# SHT_Test_Module.net
KiCad netlist of a schematic drawn in EAGLE
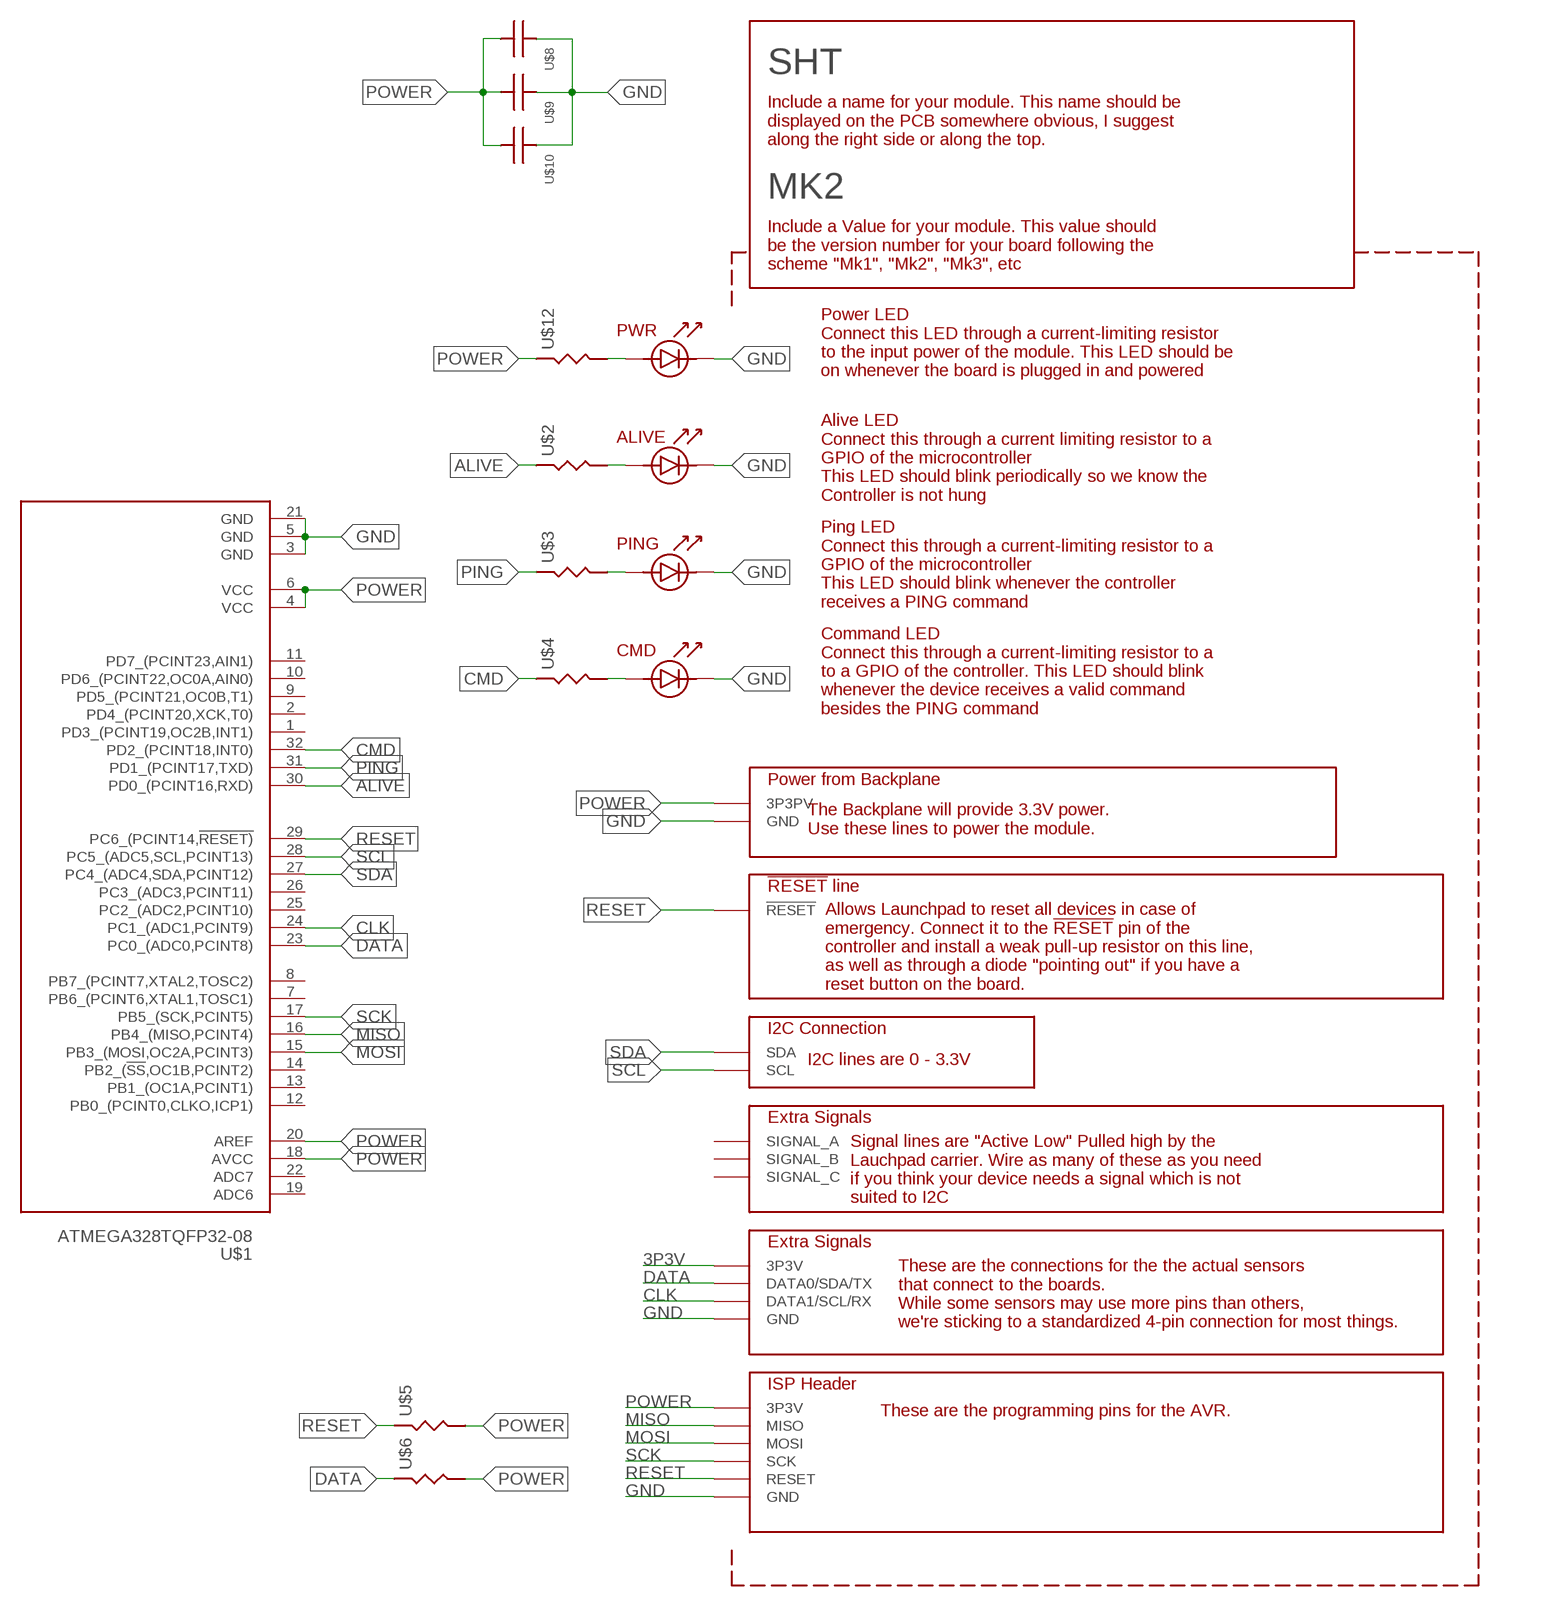
[diagram p0: schematic, sheet 1]

(export (version "E")
  (design (tool "Eeschema 10.0.6"))
  (components
    (comp (ref "SHT")
      (value "MK2")
      (footprint "eagle-import:SENSOR_MODULE_MK1")
      (libsource (lib "eagle-import") (part "SENSOR_MODULE_MK1"))
    )
    (comp (ref "U$1")
      (value "ATMEGA328TQFP32-08")
      (footprint "eagle-import:TQFP32-08")
      (libsource (lib "eagle-import") (part "ATMEGA328TQFP32-08"))
    )
    (comp (ref "U$2")
      (value "RESISTOR")
      (footprint "eagle-import:0805_STACKPOLERESISTOR")
      (libsource (lib "eagle-import") (part "RESISTOR"))
    )
    (comp (ref "U$3")
      (value "RESISTOR")
      (footprint "eagle-import:0805_STACKPOLERESISTOR")
      (libsource (lib "eagle-import") (part "RESISTOR"))
    )
    (comp (ref "U$4")
      (value "RESISTOR")
      (footprint "eagle-import:0805_STACKPOLERESISTOR")
      (libsource (lib "eagle-import") (part "RESISTOR"))
    )
    (comp (ref "U$5")
      (value "RESISTOR")
      (footprint "eagle-import:0805_STACKPOLERESISTOR")
      (libsource (lib "eagle-import") (part "RESISTOR"))
    )
    (comp (ref "U$6")
      (value "RESISTOR")
      (footprint "eagle-import:0805_STACKPOLERESISTOR")
      (libsource (lib "eagle-import") (part "RESISTOR"))
    )
    (comp (ref "U$8")
      (value "CAPACITOR-UNPOLARIZED0805")
      (footprint "eagle-import:0805_STACKPOLERESISTOR")
      (libsource (lib "eagle-import") (part "CAPACITOR-UNPOLARIZED0805"))
    )
    (comp (ref "U$9")
      (value "CAPACITOR-UNPOLARIZED0805")
      (footprint "eagle-import:0805_STACKPOLERESISTOR")
      (libsource (lib "eagle-import") (part "CAPACITOR-UNPOLARIZED0805"))
    )
    (comp (ref "U$10")
      (value "CAPACITOR-UNPOLARIZED0805")
      (footprint "eagle-import:0805_STACKPOLERESISTOR")
      (libsource (lib "eagle-import") (part "CAPACITOR-UNPOLARIZED0805"))
    )
    (comp (ref "U$12")
      (value "RESISTOR")
      (footprint "eagle-import:0805_STACKPOLERESISTOR")
      (libsource (lib "eagle-import") (part "RESISTOR"))
    )
  )
  (nets
    (net (code "1") (name "/3P3V") (class "Default")
      (node (ref "SHT") (pin "3P3V@2") (pinfunction "3P3V_3P3V@2") (pintype "bidirectional"))
      (node (ref "SHT") (pin "3P3V@3") (pinfunction "3P3V_3P3V@3") (pintype "bidirectional"))
    )
    (net (code "2") (name "ALIVE") (class "Default")
      (node (ref "U$1") (pin "30") (pinfunction "PD0_(PCINT16,RXD)_30") (pintype "bidirectional"))
      (node (ref "U$2") (pin "P$1") (pinfunction "P$1_P$1") (pintype "bidirectional"))
    )
    (net (code "3") (name "CLK") (class "Default")
      (node (ref "SHT") (pin "DATA1@1") (pinfunction "DATA1/SCL/RX_DATA1@1") (pintype "bidirectional"))
      (node (ref "SHT") (pin "DATA1@2") (pinfunction "DATA1/SCL/RX_DATA1@2") (pintype "bidirectional"))
      (node (ref "U$1") (pin "24") (pinfunction "PC1_(ADC1,PCINT9)_24") (pintype "bidirectional"))
    )
    (net (code "4") (name "CMD") (class "Default")
      (node (ref "U$1") (pin "32") (pinfunction "PD2_(PCINT18,INT0)_32") (pintype "bidirectional"))
      (node (ref "U$4") (pin "P$1") (pinfunction "P$1_P$1") (pintype "bidirectional"))
    )
    (net (code "5") (name "DATA") (class "Default")
      (node (ref "SHT") (pin "DATA0@1") (pinfunction "DATA0/SDA/TX_DATA0@1") (pintype "bidirectional"))
      (node (ref "SHT") (pin "DATA0@2") (pinfunction "DATA0/SDA/TX_DATA0@2") (pintype "bidirectional"))
      (node (ref "U$1") (pin "23") (pinfunction "PC0_(ADC0,PCINT8)_23") (pintype "bidirectional"))
      (node (ref "U$6") (pin "P$1") (pinfunction "P$1_P$1") (pintype "bidirectional"))
    )
    (net (code "6") (name "GND") (class "Default")
      (node (ref "SHT") (pin "ALIVELED_CATHODE") (pinfunction "ALIVELED_CATHODE_ALIVELED_CATHODE") (pintype "bidirectional"))
      (node (ref "SHT") (pin "CMDLED_CATHODE") (pinfunction "CMDLED_CATHODE_CMDLED_CATHODE") (pintype "bidirectional"))
      (node (ref "SHT") (pin "GND@1") (pinfunction "GND_GND@1") (pintype "bidirectional"))
      (node (ref "SHT") (pin "GND@2") (pinfunction "GND_GND@2") (pintype "bidirectional"))
      (node (ref "SHT") (pin "GND@3") (pinfunction "GND_GND@3") (pintype "bidirectional"))
      (node (ref "SHT") (pin "GND@4") (pinfunction "GND_GND@4") (pintype "bidirectional"))
      (node (ref "SHT") (pin "PINGLED_CATHODE") (pinfunction "PINGLED_CATHODE_PINGLED_CATHODE") (pintype "bidirectional"))
      (node (ref "SHT") (pin "PWRLED_CATHODE") (pinfunction "PWRLED_CATHODE_PWRLED_CATHODE") (pintype "bidirectional"))
      (node (ref "U$1") (pin "21") (pinfunction "GND_21") (pintype "bidirectional"))
      (node (ref "U$1") (pin "3") (pinfunction "GND_3") (pintype "bidirectional"))
      (node (ref "U$1") (pin "5") (pinfunction "GND_5") (pintype "bidirectional"))
      (node (ref "U$10") (pin "P$1") (pinfunction "P$1_P$1") (pintype "bidirectional"))
      (node (ref "U$8") (pin "P$1") (pinfunction "P$1_P$1") (pintype "bidirectional"))
      (node (ref "U$9") (pin "P$1") (pinfunction "P$1_P$1") (pintype "bidirectional"))
    )
    (net (code "7") (name "MISO") (class "Default")
      (node (ref "SHT") (pin "MISO") (pinfunction "MISO_MISO") (pintype "bidirectional"))
      (node (ref "U$1") (pin "16") (pinfunction "PB4_(MISO,PCINT4)_16") (pintype "bidirectional"))
    )
    (net (code "8") (name "MOSI") (class "Default")
      (node (ref "SHT") (pin "MOSI") (pinfunction "MOSI_MOSI") (pintype "bidirectional"))
      (node (ref "U$1") (pin "15") (pinfunction "PB3_(MOSI,OC2A,PCINT3)_15") (pintype "bidirectional"))
    )
    (net (code "9") (name "Net-(SHT-PadALIVELED_ANODE)") (class "Default")
      (node (ref "SHT") (pin "ALIVELED_ANODE") (pinfunction "ALIVELED_ANODE_ALIVELED_ANODE") (pintype "bidirectional"))
      (node (ref "U$2") (pin "P$2") (pinfunction "P$2_P$2") (pintype "bidirectional"))
    )
    (net (code "10") (name "Net-(SHT-PadCMDLED_ANODE)") (class "Default")
      (node (ref "SHT") (pin "CMDLED_ANODE") (pinfunction "CMDLED_ANODE_CMDLED_ANODE") (pintype "bidirectional"))
      (node (ref "U$4") (pin "P$2") (pinfunction "P$2_P$2") (pintype "bidirectional"))
    )
    (net (code "11") (name "Net-(SHT-PadPINGLED_ANODE)") (class "Default")
      (node (ref "SHT") (pin "PINGLED_ANODE") (pinfunction "PINGLED_ANODE_PINGLED_ANODE") (pintype "bidirectional"))
      (node (ref "U$3") (pin "P$2") (pinfunction "P$2_P$2") (pintype "bidirectional"))
    )
    (net (code "12") (name "Net-(SHT-PadPWRLED_ANODE)") (class "Default")
      (node (ref "SHT") (pin "PWRLED_ANODE") (pinfunction "PWRLED_ANODE_PWRLED_ANODE") (pintype "bidirectional"))
      (node (ref "U$12") (pin "P$2") (pinfunction "P$2_P$2") (pintype "bidirectional"))
    )
    (net (code "13") (name "PING") (class "Default")
      (node (ref "U$1") (pin "31") (pinfunction "PD1_(PCINT17,TXD)_31") (pintype "bidirectional"))
      (node (ref "U$3") (pin "P$1") (pinfunction "P$1_P$1") (pintype "bidirectional"))
    )
    (net (code "14") (name "POWER") (class "Default")
      (node (ref "SHT") (pin "3P3V@1") (pinfunction "3P3PV_3P3V@1") (pintype "bidirectional"))
      (node (ref "SHT") (pin "3P3V@4") (pinfunction "3P3V_3P3V@4") (pintype "bidirectional"))
      (node (ref "U$1") (pin "18") (pinfunction "AVCC_18") (pintype "bidirectional"))
      (node (ref "U$1") (pin "20") (pinfunction "AREF_20") (pintype "bidirectional"))
      (node (ref "U$1") (pin "4") (pinfunction "VCC_4") (pintype "bidirectional"))
      (node (ref "U$1") (pin "6") (pinfunction "VCC_6") (pintype "bidirectional"))
      (node (ref "U$10") (pin "P$2") (pinfunction "P$2_P$2") (pintype "bidirectional"))
      (node (ref "U$12") (pin "P$1") (pinfunction "P$1_P$1") (pintype "bidirectional"))
      (node (ref "U$5") (pin "P$2") (pinfunction "P$2_P$2") (pintype "bidirectional"))
      (node (ref "U$6") (pin "P$2") (pinfunction "P$2_P$2") (pintype "bidirectional"))
      (node (ref "U$8") (pin "P$2") (pinfunction "P$2_P$2") (pintype "bidirectional"))
      (node (ref "U$9") (pin "P$2") (pinfunction "P$2_P$2") (pintype "bidirectional"))
    )
    (net (code "15") (name "RESET") (class "Default")
      (node (ref "SHT") (pin "RESET@1") (pinfunction "~{RESET}_RESET@1") (pintype "bidirectional"))
      (node (ref "SHT") (pin "RESET@2") (pinfunction "RESET_RESET@2") (pintype "bidirectional"))
      (node (ref "U$1") (pin "29") (pinfunction "PC6_(PCINT14,~{RESET})_29") (pintype "bidirectional"))
      (node (ref "U$5") (pin "P$1") (pinfunction "P$1_P$1") (pintype "bidirectional"))
    )
    (net (code "16") (name "SCK") (class "Default")
      (node (ref "SHT") (pin "SCK") (pinfunction "SCK_SCK") (pintype "bidirectional"))
      (node (ref "U$1") (pin "17") (pinfunction "PB5_(SCK,PCINT5)_17") (pintype "bidirectional"))
    )
    (net (code "17") (name "SCL") (class "Default")
      (node (ref "SHT") (pin "SCL") (pinfunction "SCL_SCL") (pintype "bidirectional"))
      (node (ref "U$1") (pin "28") (pinfunction "PC5_(ADC5,SCL,PCINT13)_28") (pintype "bidirectional"))
    )
    (net (code "18") (name "SDA") (class "Default")
      (node (ref "SHT") (pin "SDA") (pinfunction "SDA_SDA") (pintype "bidirectional"))
      (node (ref "U$1") (pin "27") (pinfunction "PC4_(ADC4,SDA,PCINT12)_27") (pintype "bidirectional"))
    )
    (net (code "19") (name "unconnected-(SHT-SIGNAL_A-PadA)") (class "Default")
      (node (ref "SHT") (pin "A") (pinfunction "SIGNAL_A_A") (pintype "bidirectional"))
    )
    (net (code "20") (name "unconnected-(SHT-SIGNAL_B-PadB)") (class "Default")
      (node (ref "SHT") (pin "B") (pinfunction "SIGNAL_B_B") (pintype "bidirectional"))
    )
    (net (code "21") (name "unconnected-(SHT-SIGNAL_C-PadC)") (class "Default")
      (node (ref "SHT") (pin "C") (pinfunction "SIGNAL_C_C") (pintype "bidirectional"))
    )
    (net (code "22") (name "unconnected-(U$1-ADC6-Pad19)") (class "Default")
      (node (ref "U$1") (pin "19") (pinfunction "ADC6_19") (pintype "bidirectional"))
    )
    (net (code "23") (name "unconnected-(U$1-ADC7-Pad22)") (class "Default")
      (node (ref "U$1") (pin "22") (pinfunction "ADC7_22") (pintype "bidirectional"))
    )
    (net (code "24") (name "unconnected-(U$1-PB0_(PCINT0,CLKO,ICP1)-Pad12)") (class "Default")
      (node (ref "U$1") (pin "12") (pinfunction "PB0_(PCINT0,CLKO,ICP1)_12") (pintype "bidirectional"))
    )
    (net (code "25") (name "unconnected-(U$1-PB1_(OC1A,PCINT1)-Pad13)") (class "Default")
      (node (ref "U$1") (pin "13") (pinfunction "PB1_(OC1A,PCINT1)_13") (pintype "bidirectional"))
    )
    (net (code "26") (name "unconnected-(U$1-PB2_(~{SS,OC1B,PCINT2})-Pad14)") (class "Default")
      (node (ref "U$1") (pin "14") (pinfunction "PB2_(~{SS,OC1B,PCINT2})_14") (pintype "bidirectional"))
    )
    (net (code "27") (name "unconnected-(U$1-PB6_(PCINT6,XTAL1,TOSC1)-Pad7)") (class "Default")
      (node (ref "U$1") (pin "7") (pinfunction "PB6_(PCINT6,XTAL1,TOSC1)_7") (pintype "bidirectional"))
    )
    (net (code "28") (name "unconnected-(U$1-PB7_(PCINT7,XTAL2,TOSC2)-Pad8)") (class "Default")
      (node (ref "U$1") (pin "8") (pinfunction "PB7_(PCINT7,XTAL2,TOSC2)_8") (pintype "bidirectional"))
    )
    (net (code "29") (name "unconnected-(U$1-PC2_(ADC2,PCINT10)-Pad25)") (class "Default")
      (node (ref "U$1") (pin "25") (pinfunction "PC2_(ADC2,PCINT10)_25") (pintype "bidirectional"))
    )
    (net (code "30") (name "unconnected-(U$1-PC3_(ADC3,PCINT11)-Pad26)") (class "Default")
      (node (ref "U$1") (pin "26") (pinfunction "PC3_(ADC3,PCINT11)_26") (pintype "bidirectional"))
    )
    (net (code "31") (name "unconnected-(U$1-PD3_(PCINT19,OC2B,INT1)-Pad1)") (class "Default")
      (node (ref "U$1") (pin "1") (pinfunction "PD3_(PCINT19,OC2B,INT1)_1") (pintype "bidirectional"))
    )
    (net (code "32") (name "unconnected-(U$1-PD4_(PCINT20,XCK,T0)-Pad2)") (class "Default")
      (node (ref "U$1") (pin "2") (pinfunction "PD4_(PCINT20,XCK,T0)_2") (pintype "bidirectional"))
    )
    (net (code "33") (name "unconnected-(U$1-PD5_(PCINT21,OC0B,T1)-Pad9)") (class "Default")
      (node (ref "U$1") (pin "9") (pinfunction "PD5_(PCINT21,OC0B,T1)_9") (pintype "bidirectional"))
    )
    (net (code "34") (name "unconnected-(U$1-PD6_(PCINT22,OC0A,AIN0)-Pad10)") (class "Default")
      (node (ref "U$1") (pin "10") (pinfunction "PD6_(PCINT22,OC0A,AIN0)_10") (pintype "bidirectional"))
    )
    (net (code "35") (name "unconnected-(U$1-PD7_(PCINT23,AIN1)-Pad11)") (class "Default")
      (node (ref "U$1") (pin "11") (pinfunction "PD7_(PCINT23,AIN1)_11") (pintype "bidirectional"))
    )
  )
)
